# mcp.net
KiCad netlist of a schematic drawn in Altium Designer
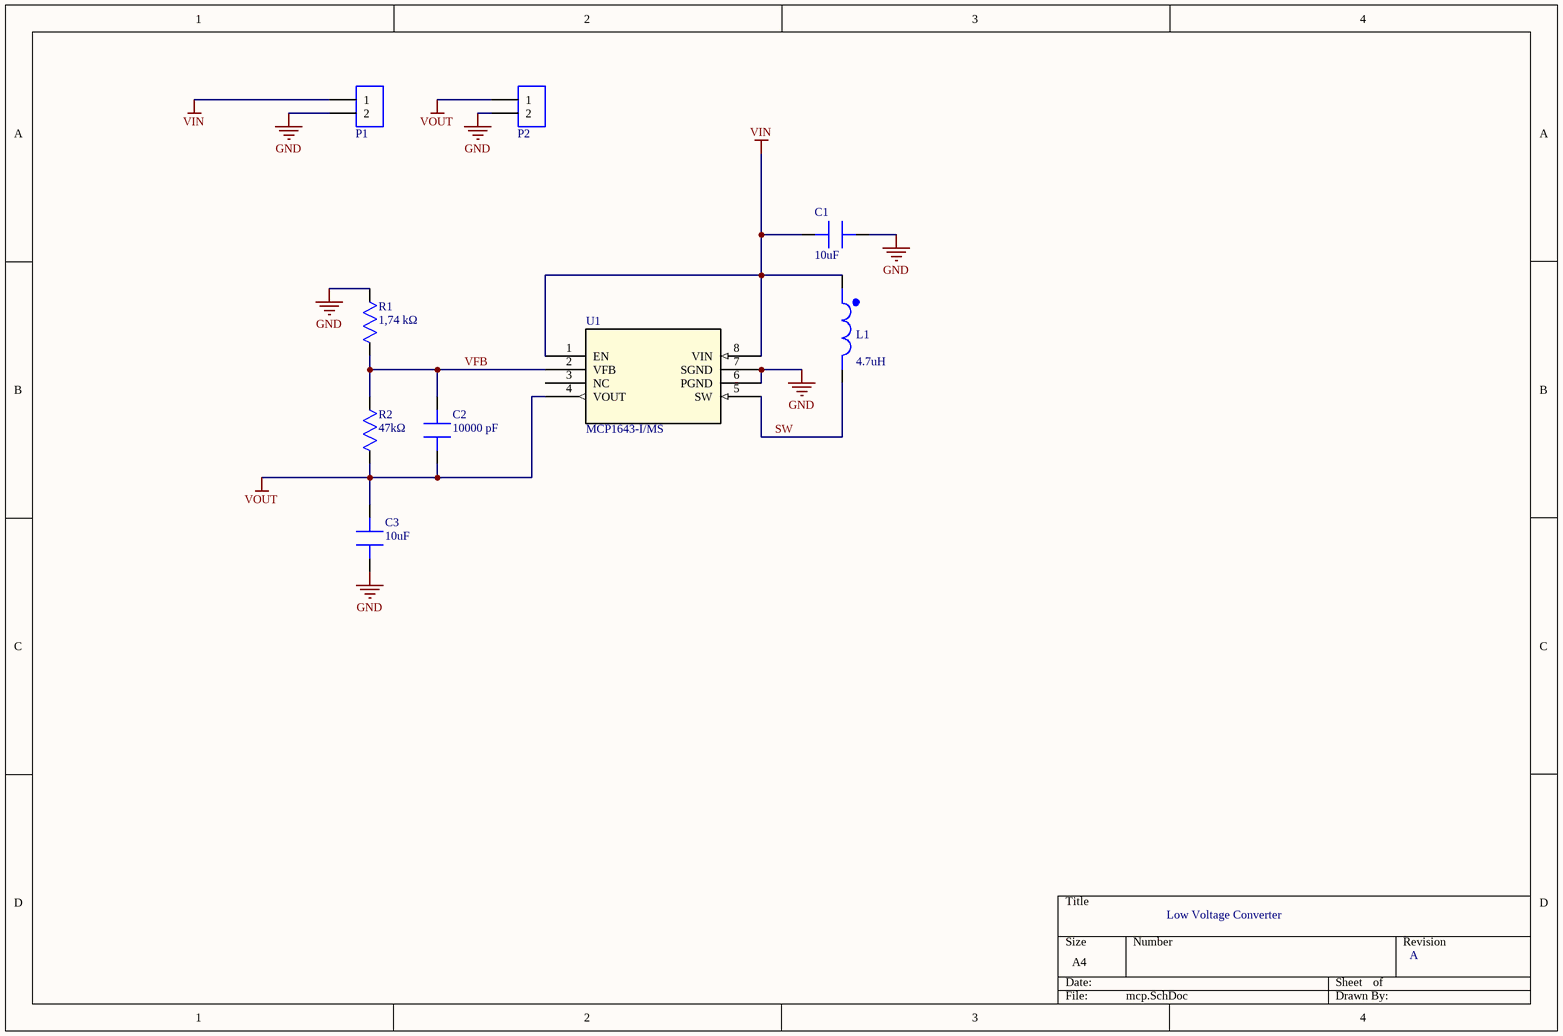
[diagram p0: mcp.SchDoc]

(export (version "E")
  (design (tool "Eeschema 10.0.6"))
  (components
    (comp (ref "C1")
      (value "10uF")
      (footprint "FB_28C0236-0JW-10")
      (description "Tantalum Capacitors - Solid Leaded 10V 10uF 10% ESR=5 Ohm")
      (fields
        (field (name "MANUFACTURER") "Kyocera AVX")
        (field (name "MANUFACTURER PART NUMBER") "TAP106K010CCS")
      )
      (libsource (lib "mcpLib") (part "TAP106K010CCS"))
    )
    (comp (ref "C2")
      (value "10000 pF")
      (footprint "CAP_C315_KEM")
      (description "10000 pF ±10% 50V Ceramic Capacitor X7R Radial")
      (fields
        (field (name "MANUFACTURER_PART_NUMBER") "C315C103K5R5TA")
        (field (name "COPYRIGHT") "Copyright (C) 2022 Ultra Librarian. All rights reserved.")
      )
      (libsource (lib "mcpLib") (part "C315C103K5R5TA"))
    )
    (comp (ref "C3")
      (value "10uF")
      (footprint "FB_28C0236-0JW-10")
      (description "Tantalum Capacitors - Solid Leaded 10V 10uF 10% ESR=5 Ohm")
      (fields
        (field (name "MANUFACTURER") "Kyocera AVX")
        (field (name "MANUFACTURER PART NUMBER") "TAP106K010CCS")
      )
      (libsource (lib "mcpLib") (part "TAP106K010CCS"))
    )
    (comp (ref "L1")
      (value "4.7uH")
      (footprint "INDRD500W70D900H1220")
      (description "Inductor: wire; THT; 4.7uH; Ioper: 5A; 22.94mΩ; ±20%; Ø7.5x9.5mm")
      (libsource (lib "mcpLib") (part "COIL0608-0.0047"))
    )
    (comp (ref "P1")
      (value "2x1 terminal block")
      (footprint "mccPcb:OST_OSTTE020104")
      (description "2 Position Wire to Board Terminal Block Horizontal with Board 0.138 _3.50mm_ Through Hole")
      (fields (field (name "MF") "On Shore") (field (name "MP") "OSTTE020104"))
      (libsource (lib "mcpLib") (part "OSTTE020104"))
    )
    (comp (ref "P2")
      (value "2x1 terminal block")
      (footprint "mccPcb:OST_OSTTE020104")
      (description "2 Position Wire to Board Terminal Block Horizontal with Board 0.138 _3.50mm_ Through Hole")
      (fields (field (name "MF") "On Shore") (field (name "MP") "OSTTE020104"))
      (libsource (lib "mcpLib") (part "OSTTE020104"))
    )
    (comp (ref "R1")
      (value "1,74 kΩ")
      (footprint "RES_MRS25_VIS")
      (description "1.74 kOhms ±1% 0.6W Through Hole Resistor Axial Metal Film")
      (fields
        (field (name "MANUFACTURER_PART_NUMBER") "MRS25000C1741FCT00")
        (field (name "COPYRIGHT") "Copyright (C) 2022 Ultra Librarian. All rights reserved.")
      )
      (libsource (lib "mcpLib") (part "MRS25000C1741FCT00"))
    )
    (comp (ref "R2")
      (value "47kΩ")
      (footprint "MOF1WS-47K")
      (description "Resistor: metal oxide; THT; 47kΩ; 1W; ±5%; Ø3.2x9mm; axial")
      (fields
        (field (name "MANUFACTURER_PART_NUMBER") "MOF1WS-47K")
        (field (name "COPYRIGHT") "Copyright (C) 2022 Ultra Librarian. All rights reserved.")
      )
      (libsource (lib "mcpLib") (part "MOF1WS-47K"))
    )
    (comp (ref "U1")
      (value "MCP1643-I/MS")
      (footprint "MSOP8_MC_MCH")
      (description "Switching Voltage Regulators 0.65V-5V input LED Driver")
      (fields (field (name "COPYRIGHT") "Copyright (C) 2022 Ultra Librarian. All rights reserved."))
      (libsource (lib "mcpLib") (part "MCP1643-I/MS"))
    )
  )
  (nets
    (net (code "1") (name "/SW") (class "Default")
      (node (ref "L1") (pin "2") (pinfunction "-_2") (pintype "passive"))
      (node (ref "U1") (pin "5") (pinfunction "SW_5") (pintype "input"))
    )
    (net (code "2") (name "/VFB") (class "Default")
      (node (ref "C2") (pin "2") (pinfunction "2_2") (pintype "passive"))
      (node (ref "R1") (pin "1") (pinfunction "1_1") (pintype "passive"))
      (node (ref "R2") (pin "2") (pinfunction "2_2") (pintype "passive"))
      (node (ref "U1") (pin "2") (pinfunction "VFB_2") (pintype "passive"))
    )
    (net (code "3") (name "GND") (class "Default")
      (node (ref "C1") (pin "2") (pinfunction "2_2") (pintype "passive"))
      (node (ref "C3") (pin "2") (pinfunction "2_2") (pintype "passive"))
      (node (ref "P1") (pin "2") (pinfunction "2_2") (pintype "passive"))
      (node (ref "P2") (pin "2") (pinfunction "2_2") (pintype "passive"))
      (node (ref "R1") (pin "2") (pinfunction "2_2") (pintype "passive"))
      (node (ref "U1") (pin "6") (pinfunction "PGND_6") (pintype "power_in"))
      (node (ref "U1") (pin "7") (pinfunction "SGND_7") (pintype "power_in"))
    )
    (net (code "4") (name "VIN") (class "Default")
      (node (ref "C1") (pin "1") (pinfunction "+_1") (pintype "passive"))
      (node (ref "L1") (pin "1") (pinfunction "+_1") (pintype "passive"))
      (node (ref "P1") (pin "1") (pinfunction "1_1") (pintype "passive"))
      (node (ref "U1") (pin "1") (pinfunction "EN_1") (pintype "passive"))
      (node (ref "U1") (pin "8") (pinfunction "VIN_8") (pintype "input"))
    )
    (net (code "5") (name "VOUT") (class "Default")
      (node (ref "C2") (pin "1") (pinfunction "1_1") (pintype "passive"))
      (node (ref "C3") (pin "1") (pinfunction "+_1") (pintype "passive"))
      (node (ref "P2") (pin "1") (pinfunction "1_1") (pintype "passive"))
      (node (ref "R2") (pin "1") (pinfunction "1_1") (pintype "passive"))
      (node (ref "U1") (pin "4") (pinfunction "VOUT_4") (pintype "output"))
    )
    (net (code "6") (name "unconnected-(U1-NC-Pad3)") (class "Default")
      (node (ref "U1") (pin "3") (pinfunction "NC_3") (pintype "passive"))
    )
  )
)
